# hakko_t12.net
KiCad netlist of a schematic drawn in EAGLE
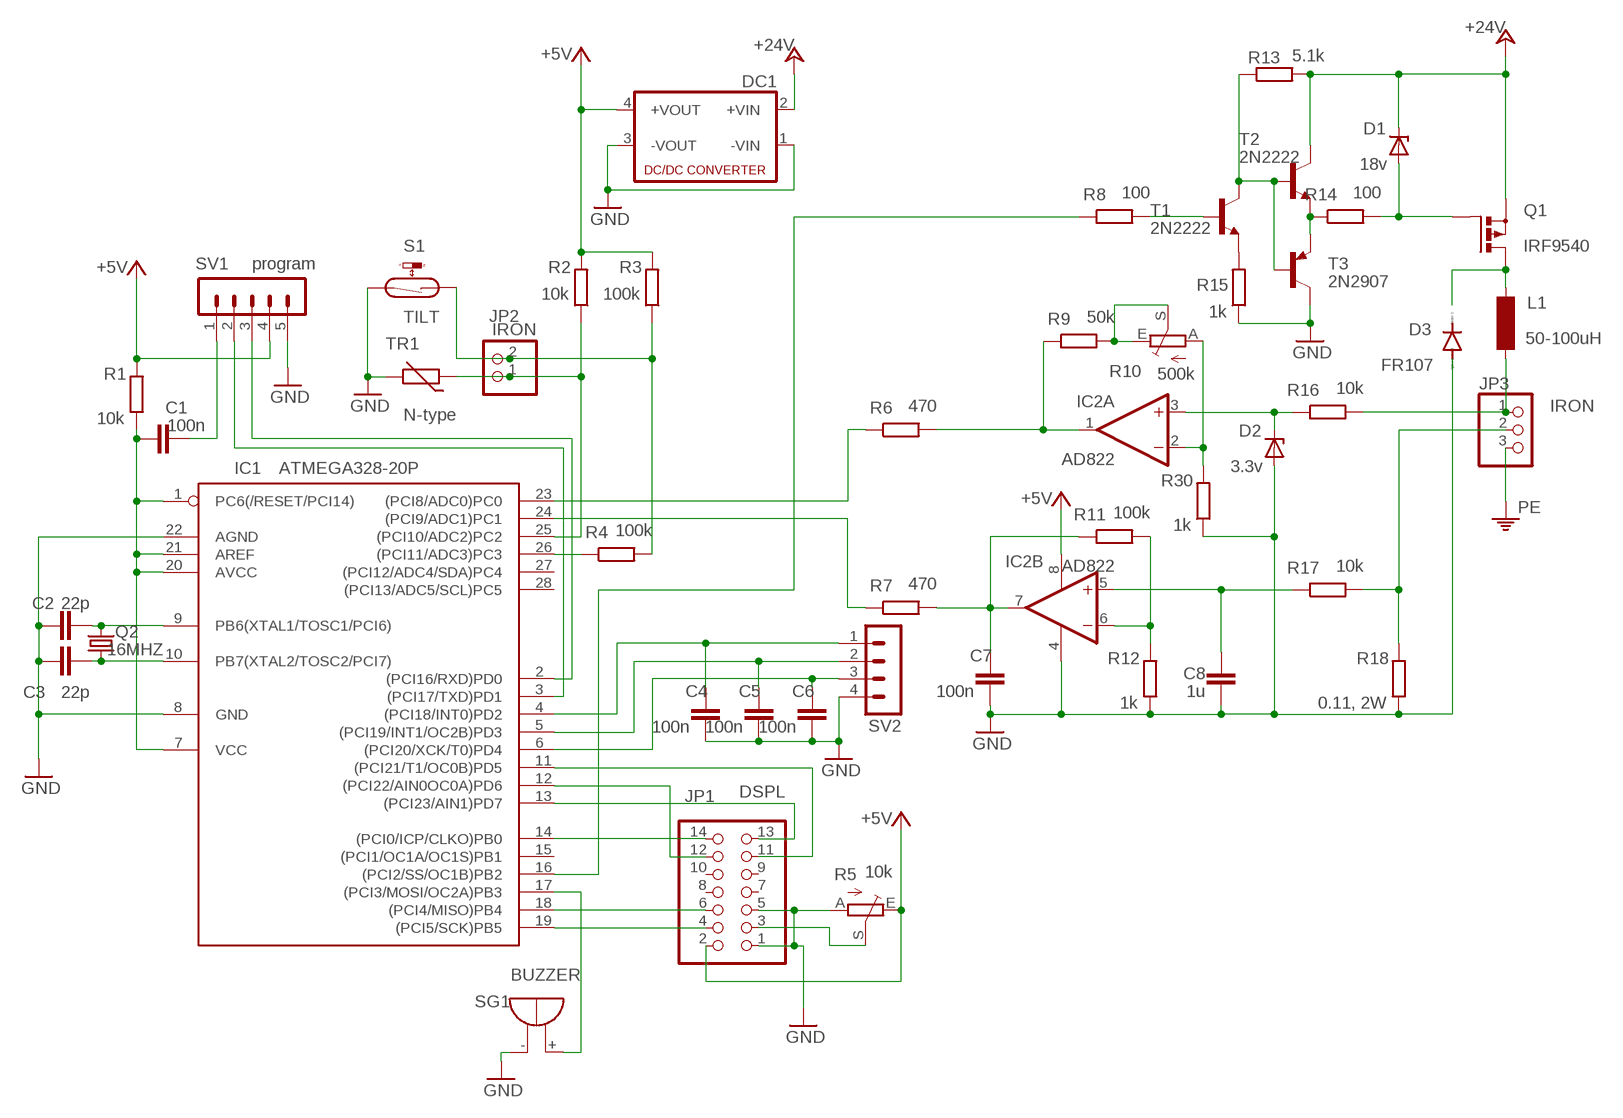
[diagram p0: schematic, sheet 1]

(export (version "E")
  (design (tool "Eeschema 10.0.6"))
  (components
    (comp (ref "C1")
      (value "100n")
      (footprint "eagle-import:C0805")
      (libsource (lib "eagle-import") (part "C-EUC0805"))
    )
    (comp (ref "C2")
      (value "22p")
      (footprint "eagle-import:C0805")
      (libsource (lib "eagle-import") (part "C-EUC0805"))
    )
    (comp (ref "C3")
      (value "22p")
      (footprint "eagle-import:C0805")
      (libsource (lib "eagle-import") (part "C-EUC0805"))
    )
    (comp (ref "C4")
      (value "100n")
      (footprint "eagle-import:C0805")
      (libsource (lib "eagle-import") (part "C-EUC0805"))
    )
    (comp (ref "C5")
      (value "100n")
      (footprint "eagle-import:C0805")
      (libsource (lib "eagle-import") (part "C-EUC0805"))
    )
    (comp (ref "C6")
      (value "100n")
      (footprint "eagle-import:C0805")
      (libsource (lib "eagle-import") (part "C-EUC0805"))
    )
    (comp (ref "C7")
      (value "100n")
      (footprint "eagle-import:C0805")
      (libsource (lib "eagle-import") (part "C-EUC0805"))
    )
    (comp (ref "C8")
      (value "1u")
      (footprint "eagle-import:C0805")
      (libsource (lib "eagle-import") (part "C-EUC0805"))
    )
    (comp (ref "D1")
      (value "18v")
      (footprint "eagle-import:C1702-15")
      (libsource (lib "eagle-import") (part "ZENER-DIODEC1702-15"))
    )
    (comp (ref "D2")
      (value "3.3v")
      (footprint "eagle-import:C1702-15")
      (libsource (lib "eagle-import") (part "ZENER-DIODEC1702-15"))
    )
    (comp (ref "D3")
      (value "FR107")
      (footprint "eagle-import:DO41-10")
      (libsource (lib "eagle-import") (part "1N4004"))
    )
    (comp (ref "DC1")
      (value "NME")
      (footprint "eagle-import:NME")
      (fields (field (name "MF") "C & D TECHNOLOGIES, INC") (field (name "MPN") "NME1205D"))
      (libsource (lib "eagle-import") (part "NME"))
    )
    (comp (ref "IC1")
      (value "ATMEGA328-20P")
      (footprint "eagle-import:DIL28-3")
      (libsource (lib "eagle-import") (part "ATMEGA328P-20"))
    )
    (comp (ref "IC2")
      (value "AD822")
      (footprint "eagle-import:DIL08")
      (libsource (lib "eagle-import") (part "MCP602P"))
    )
    (comp (ref "JP1")
      (value "DSPL")
      (footprint "eagle-import:2X07")
      (libsource (lib "eagle-import") (part "PINHD-2X7"))
    )
    (comp (ref "JP2")
      (value "IRON")
      (footprint "eagle-import:1X02")
      (libsource (lib "eagle-import") (part "PINHD-1X2"))
    )
    (comp (ref "JP3")
      (value "IRON")
      (footprint "eagle-import:1X03")
      (libsource (lib "eagle-import") (part "PINHD-1X3"))
    )
    (comp (ref "L1")
      (value "50-100uH")
      (footprint "eagle-import:SD8")
      (libsource (lib "eagle-import") (part "SD8"))
    )
    (comp (ref "Q1")
      (value "IRF9540")
      (footprint "eagle-import:TO220BH")
      (libsource (lib "eagle-import") (part "PMOSFET_PTO220BH"))
    )
    (comp (ref "Q2")
      (value "16MHZ")
      (footprint "eagle-import:HC49_S")
      (libsource (lib "eagle-import") (part "CRYSTALHC49S"))
    )
    (comp (ref "R1")
      (value "10k")
      (footprint "eagle-import:R0805")
      (libsource (lib "eagle-import") (part "R-EU_R0805"))
    )
    (comp (ref "R2")
      (value "10k")
      (footprint "eagle-import:R0805")
      (libsource (lib "eagle-import") (part "R-EU_R0805"))
    )
    (comp (ref "R3")
      (value "100k")
      (footprint "eagle-import:R0805")
      (libsource (lib "eagle-import") (part "R-EU_R0805"))
    )
    (comp (ref "R4")
      (value "100k")
      (footprint "eagle-import:R0805")
      (libsource (lib "eagle-import") (part "R-EU_R0805"))
    )
    (comp (ref "R5")
      (value "10k")
      (footprint "eagle-import:B25P")
      (libsource (lib "eagle-import") (part "TRIM_EU-B25P"))
    )
    (comp (ref "R6")
      (value "470")
      (footprint "eagle-import:R0805")
      (libsource (lib "eagle-import") (part "R-EU_R0805"))
    )
    (comp (ref "R7")
      (value "470")
      (footprint "eagle-import:R0805")
      (libsource (lib "eagle-import") (part "R-EU_R0805"))
    )
    (comp (ref "R8")
      (value "100")
      (footprint "eagle-import:R0805")
      (libsource (lib "eagle-import") (part "R-EU_R0805"))
    )
    (comp (ref "R9")
      (value "50k")
      (footprint "eagle-import:R0805")
      (libsource (lib "eagle-import") (part "R-EU_R0805"))
    )
    (comp (ref "R10")
      (value "500k")
      (footprint "eagle-import:RJ9W")
      (libsource (lib "eagle-import") (part "TRIM_EU-RJ9W"))
    )
    (comp (ref "R11")
      (value "100k")
      (footprint "eagle-import:R0805")
      (libsource (lib "eagle-import") (part "R-EU_R0805"))
    )
    (comp (ref "R12")
      (value "1k")
      (footprint "eagle-import:R0805")
      (libsource (lib "eagle-import") (part "R-EU_R0805"))
    )
    (comp (ref "R13")
      (value "5.1k")
      (footprint "eagle-import:R0805")
      (libsource (lib "eagle-import") (part "R-EU_R0805"))
    )
    (comp (ref "R14")
      (value "100")
      (footprint "eagle-import:R0805")
      (libsource (lib "eagle-import") (part "R-EU_R0805"))
    )
    (comp (ref "R15")
      (value "1k")
      (footprint "eagle-import:R0805")
      (libsource (lib "eagle-import") (part "R-EU_R0805"))
    )
    (comp (ref "R16")
      (value "10k")
      (footprint "eagle-import:R0805")
      (libsource (lib "eagle-import") (part "R-EU_R0805"))
    )
    (comp (ref "R17")
      (value "10k")
      (footprint "eagle-import:R0805")
      (libsource (lib "eagle-import") (part "R-EU_R0805"))
    )
    (comp (ref "R18")
      (value "0.11, 2W")
      (footprint "eagle-import:R0805")
      (libsource (lib "eagle-import") (part "R-EU_R0805"))
    )
    (comp (ref "R30")
      (value "1k")
      (footprint "eagle-import:R0805")
      (libsource (lib "eagle-import") (part "R-EU_R0805"))
    )
    (comp (ref "S1")
      (value "TILT")
      (footprint "eagle-import:CT10-A2")
      (libsource (lib "eagle-import") (part "REED-SWITCH-CT10-A2"))
    )
    (comp (ref "SG1")
      (value "BUZZER")
      (footprint "eagle-import:EB2209A")
      (libsource (lib "eagle-import") (part "EB2209A"))
    )
    (comp (ref "SV1")
      (value "program")
      (footprint "eagle-import:MA05-1")
      (libsource (lib "eagle-import") (part "MA05-1"))
    )
    (comp (ref "SV2")
      (value "MA04-1")
      (footprint "eagle-import:MA04-1")
      (libsource (lib "eagle-import") (part "MA04-1"))
    )
    (comp (ref "T1")
      (value "2N2222")
      (footprint "eagle-import:TO18")
      (libsource (lib "eagle-import") (part "2N2222"))
    )
    (comp (ref "T2")
      (value "2N2222")
      (footprint "eagle-import:TO18")
      (libsource (lib "eagle-import") (part "2N2222"))
    )
    (comp (ref "T3")
      (value "2N2907")
      (footprint "eagle-import:TO18")
      (libsource (lib "eagle-import") (part "-PNP-TO18-EBC2N2907"))
    )
    (comp (ref "TR1")
      (value "N-type")
      (footprint "eagle-import:R-5")
      (libsource (lib "eagle-import") (part "THERMISTOR_R-5"))
    )
  )
  (nets
    (net (code "1") (name "+5V") (class "Default")
      (node (ref "DC1") (pin "4") (pinfunction "+VOUT_4") (pintype "passive"))
      (node (ref "IC2") (pin "8") (pinfunction "V+_8") (pintype "power_in"))
      (node (ref "JP1") (pin "2") (pinfunction "2_2") (pintype "passive"))
      (node (ref "R1") (pin "2") (pinfunction "2_2") (pintype "passive"))
      (node (ref "R2") (pin "2") (pinfunction "2_2") (pintype "passive"))
      (node (ref "R3") (pin "2") (pinfunction "2_2") (pintype "passive"))
      (node (ref "R5") (pin "E") (pinfunction "E_E") (pintype "passive"))
      (node (ref "SV1") (pin "4") (pinfunction "4_4") (pintype "passive"))
    )
    (net (code "2") (name "+24V") (class "Default")
      (node (ref "D1") (pin "C") (pinfunction "C_C") (pintype "passive"))
      (node (ref "DC1") (pin "2") (pinfunction "+VIN_2") (pintype "passive"))
      (node (ref "Q1") (pin "S") (pinfunction "S_S") (pintype "passive"))
      (node (ref "R13") (pin "2") (pinfunction "2_2") (pintype "passive"))
      (node (ref "T2") (pin "3") (pinfunction "C_3") (pintype "passive"))
    )
    (net (code "3") (name "GND") (class "Default")
      (node (ref "C2") (pin "1") (pinfunction "1_1") (pintype "passive"))
      (node (ref "C3") (pin "1") (pinfunction "1_1") (pintype "passive"))
      (node (ref "C4") (pin "2") (pinfunction "2_2") (pintype "passive"))
      (node (ref "C5") (pin "2") (pinfunction "2_2") (pintype "passive"))
      (node (ref "C6") (pin "2") (pinfunction "2_2") (pintype "passive"))
      (node (ref "C7") (pin "2") (pinfunction "2_2") (pintype "passive"))
      (node (ref "C8") (pin "2") (pinfunction "2_2") (pintype "passive"))
      (node (ref "D2") (pin "A") (pinfunction "A_A") (pintype "passive"))
      (node (ref "D3") (pin "A") (pinfunction "A_A") (pintype "passive"))
      (node (ref "DC1") (pin "1") (pinfunction "-VIN_1") (pintype "passive"))
      (node (ref "DC1") (pin "3") (pinfunction "-VOUT_3") (pintype "passive"))
      (node (ref "IC1") (pin "22") (pinfunction "AGND_22") (pintype "bidirectional"))
      (node (ref "IC1") (pin "8") (pinfunction "GND_8") (pintype "bidirectional"))
      (node (ref "IC2") (pin "4") (pinfunction "V-_4") (pintype "power_in"))
      (node (ref "JP1") (pin "1") (pinfunction "1_1") (pintype "passive"))
      (node (ref "JP1") (pin "5") (pinfunction "5_5") (pintype "passive"))
      (node (ref "R12") (pin "1") (pinfunction "1_1") (pintype "passive"))
      (node (ref "R15") (pin "1") (pinfunction "1_1") (pintype "passive"))
      (node (ref "R18") (pin "1") (pinfunction "1_1") (pintype "passive"))
      (node (ref "R30") (pin "1") (pinfunction "1_1") (pintype "passive"))
      (node (ref "R5") (pin "A") (pinfunction "A_A") (pintype "passive"))
      (node (ref "S1") (pin "2") (pinfunction "2_2") (pintype "passive"))
      (node (ref "SG1") (pin "-") (pinfunction "-_-") (pintype "passive"))
      (node (ref "SV1") (pin "5") (pinfunction "5_5") (pintype "passive"))
      (node (ref "SV2") (pin "4") (pinfunction "4_4") (pintype "passive"))
      (node (ref "T3") (pin "3") (pinfunction "C_3") (pintype "passive"))
      (node (ref "TR1") (pin "2") (pinfunction "2_2") (pintype "passive"))
    )
    (net (code "4") (name "Net-(C1-Pad2)") (class "Default")
      (node (ref "C1") (pin "2") (pinfunction "2_2") (pintype "passive"))
      (node (ref "SV1") (pin "1") (pinfunction "1_1") (pintype "passive"))
    )
    (net (code "5") (name "Net-(D1-PadA)") (class "Default")
      (node (ref "D1") (pin "A") (pinfunction "A_A") (pintype "passive"))
      (node (ref "Q1") (pin "G") (pinfunction "G_G") (pintype "passive"))
      (node (ref "R14") (pin "2") (pinfunction "2_2") (pintype "passive"))
    )
    (net (code "6") (name "Net-(IC1-(PCI0{slash}ICP{slash}CLKO)PB0)") (class "Default")
      (node (ref "IC1") (pin "14") (pinfunction "(PCI0/ICP/CLKO)PB0_14") (pintype "bidirectional"))
      (node (ref "JP1") (pin "14") (pinfunction "14_14") (pintype "passive"))
    )
    (net (code "7") (name "Net-(IC1-(PCI2{slash}SS{slash}OC1B)PB2)") (class "Default")
      (node (ref "IC1") (pin "16") (pinfunction "(PCI2/SS/OC1B)PB2_16") (pintype "bidirectional"))
      (node (ref "R8") (pin "1") (pinfunction "1_1") (pintype "passive"))
    )
    (net (code "8") (name "Net-(IC1-(PCI3{slash}MOSI{slash}OC2A)PB3)") (class "Default")
      (node (ref "IC1") (pin "17") (pinfunction "(PCI3/MOSI/OC2A)PB3_17") (pintype "bidirectional"))
      (node (ref "SG1") (pin "+") (pinfunction "+_+") (pintype "passive"))
    )
    (net (code "9") (name "Net-(IC1-(PCI4{slash}MISO)PB4)") (class "Default")
      (node (ref "IC1") (pin "18") (pinfunction "(PCI4/MISO)PB4_18") (pintype "bidirectional"))
      (node (ref "JP1") (pin "6") (pinfunction "6_6") (pintype "passive"))
    )
    (net (code "10") (name "Net-(IC1-(PCI5{slash}SCK)PB5)") (class "Default")
      (node (ref "IC1") (pin "19") (pinfunction "(PCI5/SCK)PB5_19") (pintype "bidirectional"))
      (node (ref "JP1") (pin "4") (pinfunction "4_4") (pintype "passive"))
    )
    (net (code "11") (name "Net-(IC1-(PCI8{slash}ADC0)PC0)") (class "Default")
      (node (ref "IC1") (pin "23") (pinfunction "(PCI8/ADC0)PC0_23") (pintype "bidirectional"))
      (node (ref "R6") (pin "1") (pinfunction "1_1") (pintype "passive"))
    )
    (net (code "12") (name "Net-(IC1-(PCI9{slash}ADC1)PC1)") (class "Default")
      (node (ref "IC1") (pin "24") (pinfunction "(PCI9/ADC1)PC1_24") (pintype "bidirectional"))
      (node (ref "R7") (pin "1") (pinfunction "1_1") (pintype "passive"))
    )
    (net (code "13") (name "Net-(IC1-(PCI10{slash}ADC2)PC2)") (class "Default")
      (node (ref "IC1") (pin "25") (pinfunction "(PCI10/ADC2)PC2_25") (pintype "bidirectional"))
      (node (ref "JP2") (pin "1") (pinfunction "1_1") (pintype "passive"))
      (node (ref "R2") (pin "1") (pinfunction "1_1") (pintype "passive"))
      (node (ref "TR1") (pin "1") (pinfunction "1_1") (pintype "passive"))
    )
    (net (code "14") (name "Net-(IC1-(PCI11{slash}ADC3)PC3)") (class "Default")
      (node (ref "IC1") (pin "26") (pinfunction "(PCI11/ADC3)PC3_26") (pintype "bidirectional"))
      (node (ref "R4") (pin "1") (pinfunction "1_1") (pintype "passive"))
    )
    (net (code "15") (name "Net-(IC1-(PCI16{slash}RXD)PD0)") (class "Default")
      (node (ref "IC1") (pin "2") (pinfunction "(PCI16/RXD)PD0_2") (pintype "bidirectional"))
      (node (ref "SV1") (pin "3") (pinfunction "3_3") (pintype "passive"))
    )
    (net (code "16") (name "Net-(IC1-(PCI17{slash}TXD)PD1)") (class "Default")
      (node (ref "IC1") (pin "3") (pinfunction "(PCI17/TXD)PD1_3") (pintype "bidirectional"))
      (node (ref "SV1") (pin "2") (pinfunction "2_2") (pintype "passive"))
    )
    (net (code "17") (name "Net-(IC1-(PCI18{slash}INT0)PD2)") (class "Default")
      (node (ref "C4") (pin "1") (pinfunction "1_1") (pintype "passive"))
      (node (ref "IC1") (pin "4") (pinfunction "(PCI18/INT0)PD2_4") (pintype "bidirectional"))
      (node (ref "SV2") (pin "1") (pinfunction "1_1") (pintype "passive"))
    )
    (net (code "18") (name "Net-(IC1-(PCI19{slash}INT1{slash}OC2B)PD3)") (class "Default")
      (node (ref "C5") (pin "1") (pinfunction "1_1") (pintype "passive"))
      (node (ref "IC1") (pin "5") (pinfunction "(PCI19/INT1/OC2B)PD3_5") (pintype "bidirectional"))
      (node (ref "SV2") (pin "2") (pinfunction "2_2") (pintype "passive"))
    )
    (net (code "19") (name "Net-(IC1-(PCI20{slash}XCK{slash}T0)PD4)") (class "Default")
      (node (ref "C6") (pin "1") (pinfunction "1_1") (pintype "passive"))
      (node (ref "IC1") (pin "6") (pinfunction "(PCI20/XCK/T0)PD4_6") (pintype "bidirectional"))
      (node (ref "SV2") (pin "3") (pinfunction "3_3") (pintype "passive"))
    )
    (net (code "20") (name "Net-(IC1-(PCI21{slash}T1{slash}OC0B)PD5)") (class "Default")
      (node (ref "IC1") (pin "11") (pinfunction "(PCI21/T1/OC0B)PD5_11") (pintype "bidirectional"))
      (node (ref "JP1") (pin "11") (pinfunction "11_11") (pintype "passive"))
    )
    (net (code "21") (name "Net-(IC1-(PCI22{slash}AIN0OC0A)PD6)") (class "Default")
      (node (ref "IC1") (pin "12") (pinfunction "(PCI22/AIN0OC0A)PD6_12") (pintype "bidirectional"))
      (node (ref "JP1") (pin "12") (pinfunction "12_12") (pintype "passive"))
    )
    (net (code "22") (name "Net-(IC1-(PCI23{slash}AIN1)PD7)") (class "Default")
      (node (ref "IC1") (pin "13") (pinfunction "(PCI23/AIN1)PD7_13") (pintype "bidirectional"))
      (node (ref "JP1") (pin "13") (pinfunction "13_13") (pintype "passive"))
    )
    (net (code "23") (name "Net-(IC1-AREF)") (class "Default")
      (node (ref "C1") (pin "1") (pinfunction "1_1") (pintype "passive"))
      (node (ref "IC1") (pin "1") (pinfunction "PC6(/RESET/PCI14)_1") (pintype "bidirectional"))
      (node (ref "IC1") (pin "20") (pinfunction "AVCC_20") (pintype "bidirectional"))
      (node (ref "IC1") (pin "21") (pinfunction "AREF_21") (pintype "bidirectional"))
      (node (ref "IC1") (pin "7") (pinfunction "VCC_7") (pintype "bidirectional"))
      (node (ref "R1") (pin "1") (pinfunction "1_1") (pintype "passive"))
    )
    (net (code "24") (name "Net-(IC1-PB6(XTAL1{slash}TOSC1{slash}PCI6))") (class "Default")
      (node (ref "C2") (pin "2") (pinfunction "2_2") (pintype "passive"))
      (node (ref "IC1") (pin "9") (pinfunction "PB6(XTAL1/TOSC1/PCI6)_9") (pintype "bidirectional"))
      (node (ref "Q2") (pin "2") (pinfunction "2_2") (pintype "passive"))
    )
    (net (code "25") (name "Net-(IC1-PB7(XTAL2{slash}TOSC2{slash}PCI7))") (class "Default")
      (node (ref "C3") (pin "2") (pinfunction "2_2") (pintype "passive"))
      (node (ref "IC1") (pin "10") (pinfunction "PB7(XTAL2/TOSC2/PCI7)_10") (pintype "bidirectional"))
      (node (ref "Q2") (pin "1") (pinfunction "1_1") (pintype "passive"))
    )
    (net (code "26") (name "Net-(IC2A-+IN)") (class "Default")
      (node (ref "D2") (pin "C") (pinfunction "C_C") (pintype "passive"))
      (node (ref "IC2") (pin "3") (pinfunction "+IN_3") (pintype "input"))
      (node (ref "R16") (pin "1") (pinfunction "1_1") (pintype "passive"))
    )
    (net (code "27") (name "Net-(IC2A--IN)") (class "Default")
      (node (ref "IC2") (pin "2") (pinfunction "-IN_2") (pintype "input"))
      (node (ref "R10") (pin "A") (pinfunction "A_A") (pintype "passive"))
      (node (ref "R30") (pin "2") (pinfunction "2_2") (pintype "passive"))
    )
    (net (code "28") (name "Net-(IC2A-OUT)") (class "Default")
      (node (ref "IC2") (pin "1") (pinfunction "OUT_1") (pintype "output"))
      (node (ref "R6") (pin "2") (pinfunction "2_2") (pintype "passive"))
      (node (ref "R9") (pin "1") (pinfunction "1_1") (pintype "passive"))
    )
    (net (code "29") (name "Net-(IC2B-+IN)") (class "Default")
      (node (ref "C8") (pin "1") (pinfunction "1_1") (pintype "passive"))
      (node (ref "IC2") (pin "5") (pinfunction "+IN_5") (pintype "input"))
      (node (ref "R17") (pin "1") (pinfunction "1_1") (pintype "passive"))
    )
    (net (code "30") (name "Net-(IC2B--IN)") (class "Default")
      (node (ref "IC2") (pin "6") (pinfunction "-IN_6") (pintype "input"))
      (node (ref "R11") (pin "2") (pinfunction "2_2") (pintype "passive"))
      (node (ref "R12") (pin "2") (pinfunction "2_2") (pintype "passive"))
    )
    (net (code "31") (name "Net-(IC2B-OUT)") (class "Default")
      (node (ref "C7") (pin "1") (pinfunction "1_1") (pintype "passive"))
      (node (ref "IC2") (pin "7") (pinfunction "OUT_7") (pintype "output"))
      (node (ref "R11") (pin "1") (pinfunction "1_1") (pintype "passive"))
      (node (ref "R7") (pin "2") (pinfunction "2_2") (pintype "passive"))
    )
    (net (code "32") (name "Net-(JP1-Pad3)") (class "Default")
      (node (ref "JP1") (pin "3") (pinfunction "3_3") (pintype "passive"))
      (node (ref "R5") (pin "S") (pinfunction "S_S") (pintype "passive"))
    )
    (net (code "33") (name "Net-(JP2-Pad2)") (class "Default")
      (node (ref "JP2") (pin "2") (pinfunction "2_2") (pintype "passive"))
      (node (ref "R3") (pin "1") (pinfunction "1_1") (pintype "passive"))
      (node (ref "R4") (pin "2") (pinfunction "2_2") (pintype "passive"))
      (node (ref "S1") (pin "1") (pinfunction "1_1") (pintype "passive"))
    )
    (net (code "34") (name "Net-(JP3-Pad1)") (class "Default")
      (node (ref "JP3") (pin "1") (pinfunction "1_1") (pintype "passive"))
      (node (ref "L1") (pin "1") (pinfunction "1_1") (pintype "passive"))
      (node (ref "R16") (pin "2") (pinfunction "2_2") (pintype "passive"))
    )
    (net (code "35") (name "Net-(JP3-Pad2)") (class "Default")
      (node (ref "JP3") (pin "2") (pinfunction "2_2") (pintype "passive"))
      (node (ref "R17") (pin "2") (pinfunction "2_2") (pintype "passive"))
      (node (ref "R18") (pin "2") (pinfunction "2_2") (pintype "passive"))
    )
    (net (code "36") (name "Net-(L1-Pad2)") (class "Default")
      (node (ref "L1") (pin "2") (pinfunction "2_2") (pintype "passive"))
      (node (ref "Q1") (pin "D") (pinfunction "D_D") (pintype "passive"))
    )
    (net (code "37") (name "Net-(R10-PadE)") (class "Default")
      (node (ref "R10") (pin "E") (pinfunction "E_E") (pintype "passive"))
      (node (ref "R10") (pin "S") (pinfunction "S_S") (pintype "passive"))
      (node (ref "R9") (pin "2") (pinfunction "2_2") (pintype "passive"))
    )
    (net (code "38") (name "Net-(T1-B)") (class "Default")
      (node (ref "R8") (pin "2") (pinfunction "2_2") (pintype "passive"))
      (node (ref "T1") (pin "2") (pinfunction "B_2") (pintype "passive"))
    )
    (net (code "39") (name "Net-(T1-C)") (class "Default")
      (node (ref "R13") (pin "1") (pinfunction "1_1") (pintype "passive"))
      (node (ref "T1") (pin "3") (pinfunction "C_3") (pintype "passive"))
      (node (ref "T2") (pin "2") (pinfunction "B_2") (pintype "passive"))
      (node (ref "T3") (pin "2") (pinfunction "B_2") (pintype "passive"))
    )
    (net (code "40") (name "Net-(T1-E)") (class "Default")
      (node (ref "R15") (pin "2") (pinfunction "2_2") (pintype "passive"))
      (node (ref "T1") (pin "1") (pinfunction "E_1") (pintype "passive"))
    )
    (net (code "41") (name "Net-(T2-E)") (class "Default")
      (node (ref "R14") (pin "1") (pinfunction "1_1") (pintype "passive"))
      (node (ref "T2") (pin "1") (pinfunction "E_1") (pintype "passive"))
      (node (ref "T3") (pin "1") (pinfunction "E_1") (pintype "passive"))
    )
    (net (code "42") (name "PE") (class "Default")
      (node (ref "JP3") (pin "3") (pinfunction "3_3") (pintype "passive"))
    )
    (net (code "43") (name "unconnected-(D3-PadC)") (class "Default")
      (node (ref "D3") (pin "C") (pinfunction "C_C") (pintype "passive"))
    )
    (net (code "44") (name "unconnected-(IC1-(PCI1{slash}OC1A{slash}OC1S)PB1-Pad15)") (class "Default")
      (node (ref "IC1") (pin "15") (pinfunction "(PCI1/OC1A/OC1S)PB1_15") (pintype "bidirectional"))
    )
    (net (code "45") (name "unconnected-(IC1-(PCI12{slash}ADC4{slash}SDA)PC4-Pad27)") (class "Default")
      (node (ref "IC1") (pin "27") (pinfunction "(PCI12/ADC4/SDA)PC4_27") (pintype "bidirectional"))
    )
    (net (code "46") (name "unconnected-(IC1-(PCI13{slash}ADC5{slash}SCL)PC5-Pad28)") (class "Default")
      (node (ref "IC1") (pin "28") (pinfunction "(PCI13/ADC5/SCL)PC5_28") (pintype "bidirectional"))
    )
    (net (code "47") (name "unconnected-(JP1-Pad7)") (class "Default")
      (node (ref "JP1") (pin "7") (pinfunction "7_7") (pintype "passive"))
    )
    (net (code "48") (name "unconnected-(JP1-Pad8)") (class "Default")
      (node (ref "JP1") (pin "8") (pinfunction "8_8") (pintype "passive"))
    )
    (net (code "49") (name "unconnected-(JP1-Pad9)") (class "Default")
      (node (ref "JP1") (pin "9") (pinfunction "9_9") (pintype "passive"))
    )
    (net (code "50") (name "unconnected-(JP1-Pad10)") (class "Default")
      (node (ref "JP1") (pin "10") (pinfunction "10_10") (pintype "passive"))
    )
  )
)
